# STM32.net
KiCad netlist of a schematic drawn in Altium Designer
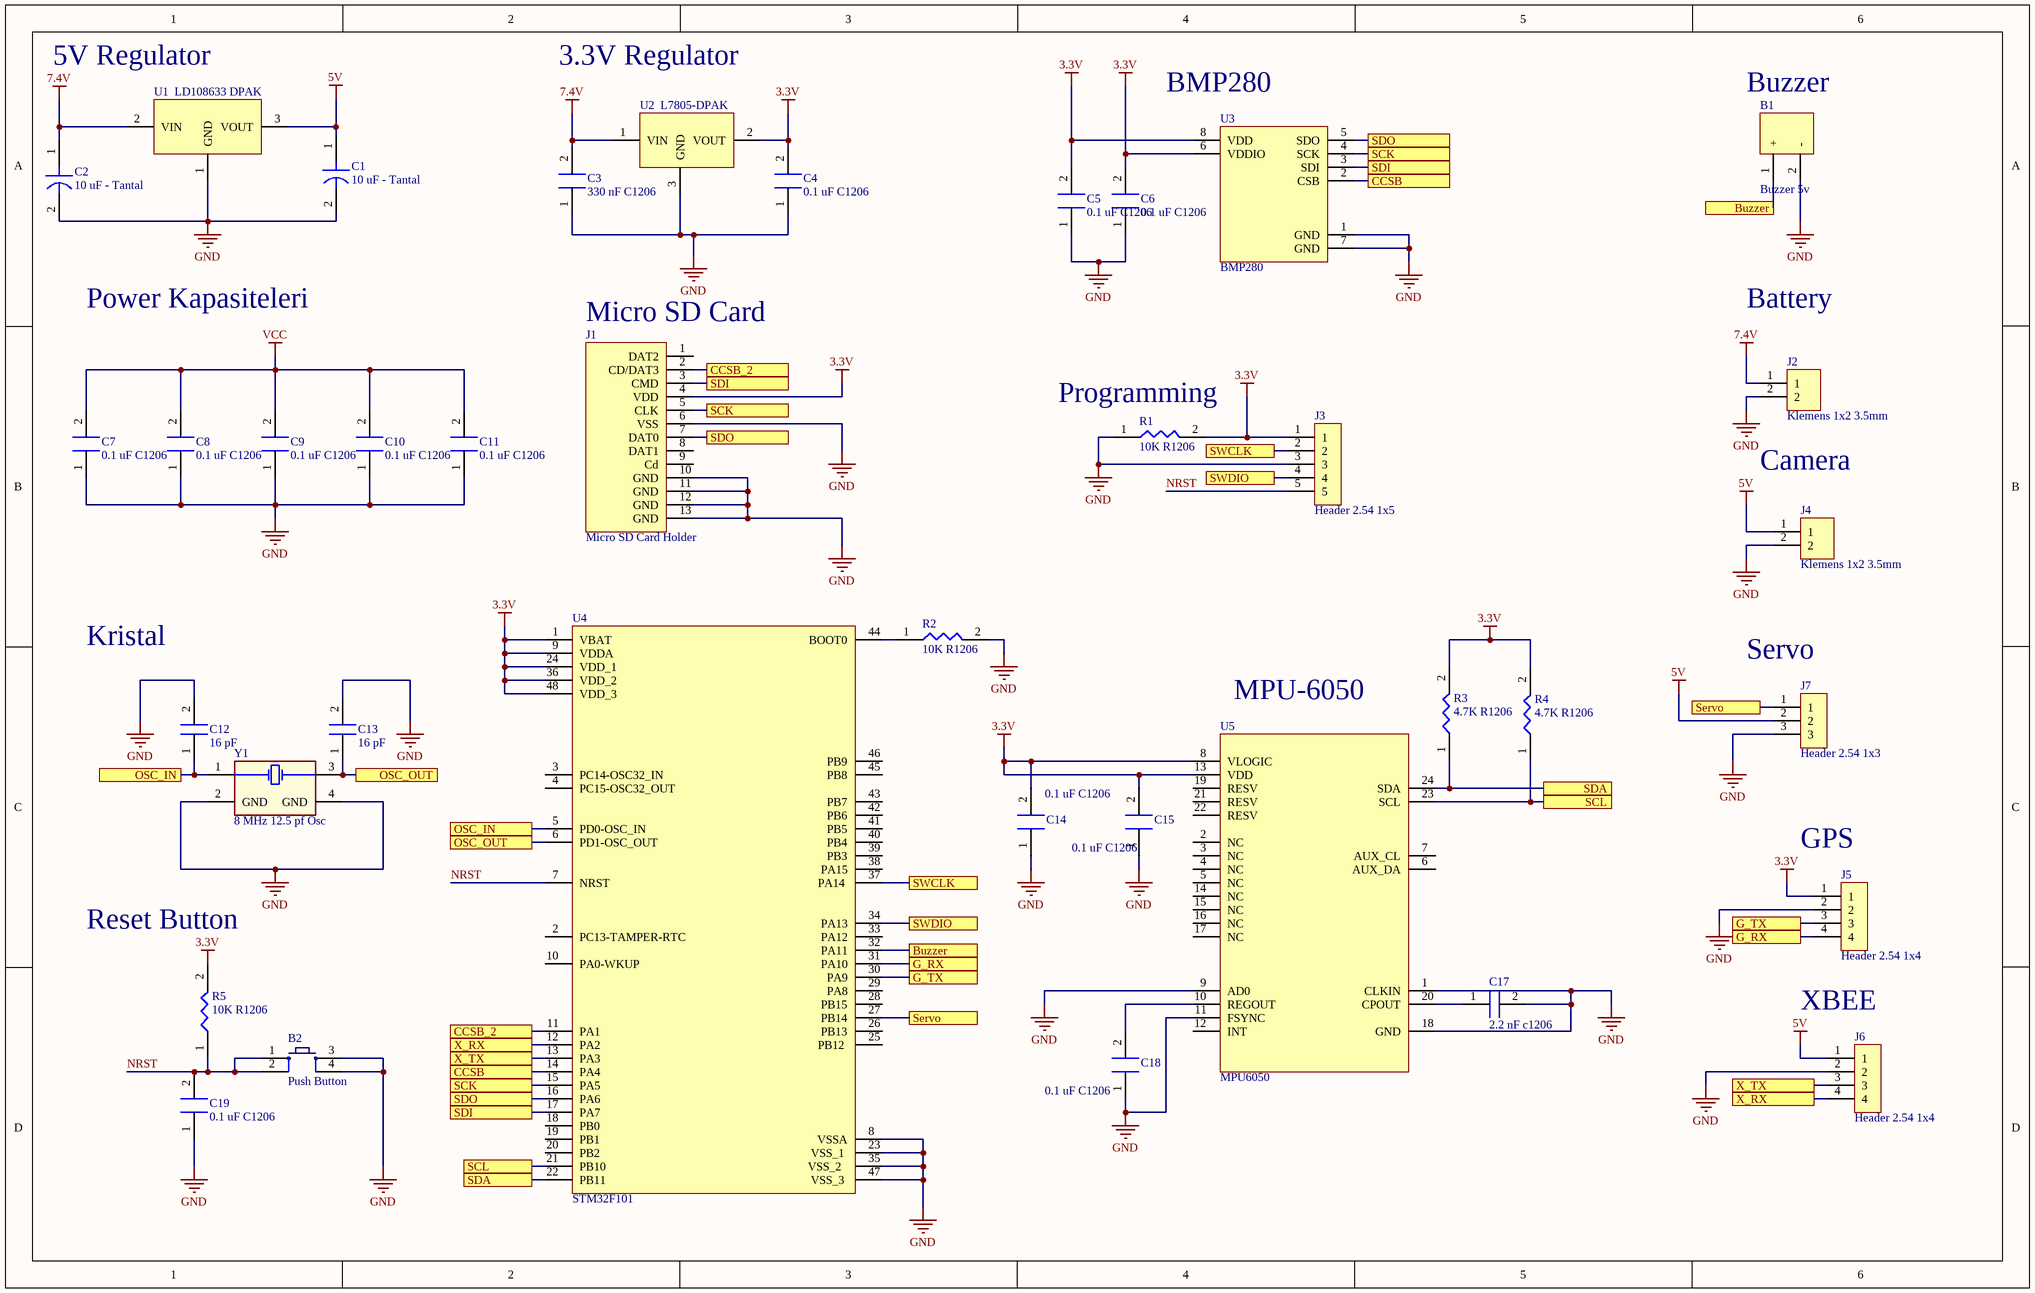
[diagram p0: STM32.SchDoc]

(export (version "E")
  (design (tool "Eeschema 10.0.6"))
  (components
    (comp (ref "B1") (value "Buzzer 5v") (footprint "Buzzer 5v") (libsource (lib "STM32") (part "Buzzer 5v")))
    (comp (ref "B2")
      (value "Push Button")
      (footprint "PUSB BUTTON-SMD")
      (description "Smd Push Button")
      (libsource (lib "STM32") (part "Push Button"))
    )
    (comp (ref "C1")
      (value "10 uF - Tantal")
      (footprint "C1206- TANTAL")
      (libsource (lib "STM32") (part "10 uF - Tantal"))
    )
    (comp (ref "C2")
      (value "10 uF - Tantal")
      (footprint "C1206- TANTAL")
      (libsource (lib "STM32") (part "10 uF - Tantal"))
    )
    (comp (ref "C3")
      (value "330 nF C1206")
      (footprint "C1206")
      (libsource (lib "STM32") (part "330 nF C1206"))
    )
    (comp (ref "C4")
      (value "0.1 uF C1206")
      (footprint "C1206")
      (libsource (lib "STM32") (part "0.1 uF C1206"))
    )
    (comp (ref "C5")
      (value "0.1 uF C1206")
      (footprint "C1206")
      (libsource (lib "STM32") (part "0.1 uF C1206"))
    )
    (comp (ref "C6")
      (value "0.1 uF C1206")
      (footprint "C1206")
      (libsource (lib "STM32") (part "0.1 uF C1206"))
    )
    (comp (ref "C7")
      (value "0.1 uF C1206")
      (footprint "C1206")
      (libsource (lib "STM32") (part "0.1 uF C1206"))
    )
    (comp (ref "C8")
      (value "0.1 uF C1206")
      (footprint "C1206")
      (libsource (lib "STM32") (part "0.1 uF C1206"))
    )
    (comp (ref "C9")
      (value "0.1 uF C1206")
      (footprint "C1206")
      (libsource (lib "STM32") (part "0.1 uF C1206"))
    )
    (comp (ref "C10")
      (value "0.1 uF C1206")
      (footprint "C1206")
      (libsource (lib "STM32") (part "0.1 uF C1206"))
    )
    (comp (ref "C11")
      (value "0.1 uF C1206")
      (footprint "C1206")
      (libsource (lib "STM32") (part "0.1 uF C1206"))
    )
    (comp (ref "C12") (value "16 pF") (footprint "C1206") (libsource (lib "STM32") (part "16 pF")))
    (comp (ref "C13") (value "16 pF") (footprint "C1206") (libsource (lib "STM32") (part "16 pF")))
    (comp (ref "C14")
      (value "0.1 uF C1206")
      (footprint "C1206")
      (libsource (lib "STM32") (part "0.1 uF C1206"))
    )
    (comp (ref "C15")
      (value "0.1 uF C1206")
      (footprint "C1206")
      (libsource (lib "STM32") (part "0.1 uF C1206"))
    )
    (comp (ref "C17")
      (value "2.2 nF c1206")
      (footprint "C1206")
      (libsource (lib "STM32") (part "2.2 nF c1206"))
    )
    (comp (ref "C18")
      (value "0.1 uF C1206")
      (footprint "C1206")
      (libsource (lib "STM32") (part "0.1 uF C1206"))
    )
    (comp (ref "C19")
      (value "0.1 uF C1206")
      (footprint "C1206")
      (libsource (lib "STM32") (part "0.1 uF C1206"))
    )
    (comp (ref "J1")
      (value "Micro SD Card Holder")
      (footprint "Micro SD Card Holder")
      (libsource (lib "STM32") (part "Micro SD Card Holder"))
    )
    (comp (ref "J2")
      (value "Klemens 1x2 3.5mm")
      (footprint "Klemens 1x2 - 3.5mm")
      (libsource (lib "STM32") (part "Klemens 1x2 3.5mm"))
    )
    (comp (ref "J3")
      (value "Header 2.54 1x5")
      (footprint "Header 2.54 1x5")
      (libsource (lib "STM32") (part "Header 2.54 1x5"))
    )
    (comp (ref "J4")
      (value "Klemens 1x2 3.5mm")
      (footprint "Klemens 1x2 - 3.5mm")
      (libsource (lib "STM32") (part "Klemens 1x2 3.5mm"))
    )
    (comp (ref "J5")
      (value "Header 2.54 1x4")
      (footprint "Header 2.54 1x4")
      (libsource (lib "STM32") (part "Header 2.54 1x4"))
    )
    (comp (ref "J6")
      (value "Header 2.54 1x4")
      (footprint "Header 2.54 1x4")
      (libsource (lib "STM32") (part "Header 2.54 1x4"))
    )
    (comp (ref "J7")
      (value "Header 2.54 1x3")
      (footprint "Header 2.54 1x3")
      (libsource (lib "STM32") (part "Header 2.54 1x3"))
    )
    (comp (ref "R1")
      (value "10K R1206")
      (footprint "R1206 Resıstor")
      (libsource (lib "STM32") (part "10K R1206"))
    )
    (comp (ref "R2")
      (value "10K R1206")
      (footprint "R1206 Resıstor")
      (libsource (lib "STM32") (part "10K R1206"))
    )
    (comp (ref "R3")
      (value "4.7K R1206")
      (footprint "R1206 Resıstor")
      (libsource (lib "STM32") (part "4.7K R1206"))
    )
    (comp (ref "R4")
      (value "4.7K R1206")
      (footprint "R1206 Resıstor")
      (libsource (lib "STM32") (part "4.7K R1206"))
    )
    (comp (ref "R5")
      (value "10K R1206")
      (footprint "R1206 Resıstor")
      (libsource (lib "STM32") (part "10K R1206"))
    )
    (comp (ref "U1")
      (value "LD108633 DPAK")
      (footprint "DPAK228P972X230-3N")
      (description "LD1086 3.3V REGULATOR")
      (libsource (lib "STM32") (part "LD108633 DPAK"))
    )
    (comp (ref "U2")
      (value "L7805-DPAK")
      (footprint "DPAK228P972X230-3N")
      (description "L7805 5V REGULATOR. SMD PAKET")
      (libsource (lib "STM32") (part "L7805-DPAK"))
    )
    (comp (ref "U3") (value "BMP280") (footprint "BMP280") (libsource (lib "STM32") (part "BMP280")))
    (comp (ref "U4")
      (value "STM32F101")
      (footprint "LQFP48-STM")
      (description "STM32F101 48 PİNLİ MİKROİŞLEMCİ")
      (libsource (lib "STM32") (part "STM32F101"))
    )
    (comp (ref "U5")
      (value "MPU6050")
      (footprint "QFN50P400X400X90_HS-25N")
      (description "MPU6050 GYRO")
      (libsource (lib "STM32") (part "MPU6050"))
    )
    (comp (ref "Y1")
      (value "8 MHz 12.5 pf Osc")
      (footprint "8 MHZ Osc.")
      (libsource (lib "STM32") (part "8 MHz 12.5 pf Osc"))
    )
  )
  (nets
    (net (code "1") (name "/Buzzer") (class "Default")
      (node (ref "B1") (pin "1") (pinfunction "+_1") (pintype "passive"))
      (node (ref "U4") (pin "32") (pinfunction "PA11_32") (pintype "passive"))
    )
    (net (code "2") (name "/CCSB") (class "Default")
      (node (ref "U3") (pin "2") (pinfunction "CSB_2") (pintype "passive"))
      (node (ref "U4") (pin "14") (pinfunction "PA4_14") (pintype "passive"))
    )
    (net (code "3") (name "/CCSB_2") (class "Default")
      (node (ref "J1") (pin "2") (pinfunction "CD/DAT3_2") (pintype "passive"))
      (node (ref "U4") (pin "11") (pinfunction "PA1_11") (pintype "passive"))
    )
    (net (code "4") (name "/G_RX") (class "Default")
      (node (ref "J5") (pin "4") (pinfunction "4_4") (pintype "passive"))
      (node (ref "U4") (pin "31") (pinfunction "PA10_31") (pintype "passive"))
    )
    (net (code "5") (name "/G_TX") (class "Default")
      (node (ref "J5") (pin "3") (pinfunction "3_3") (pintype "passive"))
      (node (ref "U4") (pin "30") (pinfunction "PA9_30") (pintype "passive"))
    )
    (net (code "6") (name "/NRST") (class "Default")
      (node (ref "B2") (pin "1") (pinfunction "1_1") (pintype "passive"))
      (node (ref "B2") (pin "2") (pinfunction "2_2") (pintype "passive"))
      (node (ref "C19") (pin "2") (pinfunction "2_2") (pintype "passive"))
      (node (ref "J3") (pin "5") (pinfunction "5_5") (pintype "passive"))
      (node (ref "R5") (pin "1") (pinfunction "1_1") (pintype "passive"))
      (node (ref "U4") (pin "7") (pinfunction "NRST_7") (pintype "passive"))
    )
    (net (code "7") (name "/OSC_IN") (class "Default")
      (node (ref "C12") (pin "1") (pinfunction "1_1") (pintype "passive"))
      (node (ref "U4") (pin "5") (pinfunction "PD0-OSC_IN_5") (pintype "passive"))
      (node (ref "Y1") (pin "1") (pintype "power_in"))
    )
    (net (code "8") (name "/OSC_OUT") (class "Default")
      (node (ref "C13") (pin "1") (pinfunction "1_1") (pintype "passive"))
      (node (ref "U4") (pin "6") (pinfunction "PD1-OSC_OUT_6") (pintype "passive"))
      (node (ref "Y1") (pin "3") (pintype "passive"))
    )
    (net (code "9") (name "/SCK") (class "Default")
      (node (ref "J1") (pin "5") (pinfunction "CLK_5") (pintype "passive"))
      (node (ref "U3") (pin "4") (pinfunction "SCK_4") (pintype "passive"))
      (node (ref "U4") (pin "15") (pinfunction "PA5_15") (pintype "passive"))
    )
    (net (code "10") (name "/SCL") (class "Default")
      (node (ref "R4") (pin "1") (pinfunction "1_1") (pintype "passive"))
      (node (ref "U4") (pin "21") (pinfunction "PB10_21") (pintype "passive"))
      (node (ref "U5") (pin "23") (pinfunction "SCL_23") (pintype "passive"))
    )
    (net (code "11") (name "/SDA") (class "Default")
      (node (ref "R3") (pin "1") (pinfunction "1_1") (pintype "passive"))
      (node (ref "U4") (pin "22") (pinfunction "PB11_22") (pintype "passive"))
      (node (ref "U5") (pin "24") (pinfunction "SDA_24") (pintype "passive"))
    )
    (net (code "12") (name "/SDI") (class "Default")
      (node (ref "J1") (pin "3") (pinfunction "CMD_3") (pintype "passive"))
      (node (ref "U3") (pin "3") (pinfunction "SDI_3") (pintype "passive"))
      (node (ref "U4") (pin "17") (pinfunction "PA7_17") (pintype "passive"))
    )
    (net (code "13") (name "/SDO") (class "Default")
      (node (ref "J1") (pin "7") (pinfunction "DAT0_7") (pintype "passive"))
      (node (ref "U3") (pin "5") (pinfunction "SDO_5") (pintype "passive"))
      (node (ref "U4") (pin "16") (pinfunction "PA6_16") (pintype "passive"))
    )
    (net (code "14") (name "/SWCLK") (class "Default")
      (node (ref "J3") (pin "2") (pinfunction "2_2") (pintype "passive"))
      (node (ref "U4") (pin "37") (pinfunction "PA14_37") (pintype "passive"))
    )
    (net (code "15") (name "/SWDIO") (class "Default")
      (node (ref "J3") (pin "4") (pinfunction "4_4") (pintype "passive"))
      (node (ref "U4") (pin "34") (pinfunction "PA13_34") (pintype "passive"))
    )
    (net (code "16") (name "/Servo") (class "Default")
      (node (ref "J7") (pin "1") (pinfunction "1_1") (pintype "passive"))
      (node (ref "U4") (pin "27") (pinfunction "PB14_27") (pintype "passive"))
    )
    (net (code "17") (name "/X_RX") (class "Default")
      (node (ref "J6") (pin "4") (pinfunction "4_4") (pintype "passive"))
      (node (ref "U4") (pin "12") (pinfunction "PA2_12") (pintype "passive"))
    )
    (net (code "18") (name "/X_TX") (class "Default")
      (node (ref "J6") (pin "3") (pinfunction "3_3") (pintype "passive"))
      (node (ref "U4") (pin "13") (pinfunction "PA3_13") (pintype "passive"))
    )
    (net (code "19") (name "3.3V") (class "Default")
      (node (ref "C14") (pin "2") (pinfunction "2_2") (pintype "passive"))
      (node (ref "C15") (pin "2") (pinfunction "2_2") (pintype "passive"))
      (node (ref "C4") (pin "2") (pinfunction "2_2") (pintype "passive"))
      (node (ref "C5") (pin "2") (pinfunction "2_2") (pintype "passive"))
      (node (ref "C6") (pin "2") (pinfunction "2_2") (pintype "passive"))
      (node (ref "J1") (pin "4") (pinfunction "VDD_4") (pintype "passive"))
      (node (ref "J3") (pin "1") (pinfunction "1_1") (pintype "passive"))
      (node (ref "J5") (pin "1") (pinfunction "1_1") (pintype "passive"))
      (node (ref "R1") (pin "2") (pinfunction "2_2") (pintype "passive"))
      (node (ref "R3") (pin "2") (pinfunction "2_2") (pintype "passive"))
      (node (ref "R4") (pin "2") (pinfunction "2_2") (pintype "passive"))
      (node (ref "R5") (pin "2") (pinfunction "2_2") (pintype "passive"))
      (node (ref "U2") (pin "2") (pinfunction "VOUT_2") (pintype "passive"))
      (node (ref "U3") (pin "6") (pinfunction "VDDIO_6") (pintype "passive"))
      (node (ref "U3") (pin "8") (pinfunction "VDD_8") (pintype "passive"))
      (node (ref "U4") (pin "1") (pinfunction "VBAT_1") (pintype "passive"))
      (node (ref "U4") (pin "24") (pinfunction "VDD_1_24") (pintype "passive"))
      (node (ref "U4") (pin "36") (pinfunction "VDD_2_36") (pintype "passive"))
      (node (ref "U4") (pin "48") (pinfunction "VDD_3_48") (pintype "passive"))
      (node (ref "U4") (pin "9") (pinfunction "VDDA_9") (pintype "passive"))
      (node (ref "U5") (pin "13") (pinfunction "VDD_13") (pintype "passive"))
      (node (ref "U5") (pin "8") (pinfunction "VLOGIC_8") (pintype "passive"))
    )
    (net (code "20") (name "5V") (class "Default")
      (node (ref "C1") (pin "1") (pinfunction "1_1") (pintype "passive"))
      (node (ref "J4") (pin "1") (pinfunction "1_1") (pintype "passive"))
      (node (ref "J6") (pin "1") (pinfunction "1_1") (pintype "passive"))
      (node (ref "J7") (pin "2") (pinfunction "2_2") (pintype "passive"))
      (node (ref "U1") (pin "3") (pinfunction "VOUT_3") (pintype "passive"))
    )
    (net (code "21") (name "7.4V") (class "Default")
      (node (ref "C2") (pin "1") (pinfunction "1_1") (pintype "passive"))
      (node (ref "C3") (pin "2") (pinfunction "2_2") (pintype "passive"))
      (node (ref "J2") (pin "1") (pinfunction "1_1") (pintype "passive"))
      (node (ref "U1") (pin "2") (pinfunction "VIN_2") (pintype "passive"))
      (node (ref "U2") (pin "1") (pinfunction "VIN_1") (pintype "passive"))
    )
    (net (code "22") (name "GND") (class "Default")
      (node (ref "B1") (pin "2") (pinfunction "-_2") (pintype "passive"))
      (node (ref "B2") (pin "3") (pinfunction "3_3") (pintype "passive"))
      (node (ref "B2") (pin "4") (pinfunction "4_4") (pintype "passive"))
      (node (ref "C1") (pin "2") (pinfunction "2_2") (pintype "passive"))
      (node (ref "C10") (pin "1") (pinfunction "1_1") (pintype "passive"))
      (node (ref "C11") (pin "1") (pinfunction "1_1") (pintype "passive"))
      (node (ref "C12") (pin "2") (pinfunction "2_2") (pintype "passive"))
      (node (ref "C13") (pin "2") (pinfunction "2_2") (pintype "passive"))
      (node (ref "C14") (pin "1") (pinfunction "1_1") (pintype "passive"))
      (node (ref "C15") (pin "1") (pinfunction "1_1") (pintype "passive"))
      (node (ref "C17") (pin "2") (pinfunction "2_2") (pintype "passive"))
      (node (ref "C18") (pin "1") (pinfunction "1_1") (pintype "passive"))
      (node (ref "C19") (pin "1") (pinfunction "1_1") (pintype "passive"))
      (node (ref "C2") (pin "2") (pinfunction "2_2") (pintype "passive"))
      (node (ref "C3") (pin "1") (pinfunction "1_1") (pintype "passive"))
      (node (ref "C4") (pin "1") (pinfunction "1_1") (pintype "passive"))
      (node (ref "C5") (pin "1") (pinfunction "1_1") (pintype "passive"))
      (node (ref "C6") (pin "1") (pinfunction "1_1") (pintype "passive"))
      (node (ref "C7") (pin "1") (pinfunction "1_1") (pintype "passive"))
      (node (ref "C8") (pin "1") (pinfunction "1_1") (pintype "passive"))
      (node (ref "C9") (pin "1") (pinfunction "1_1") (pintype "passive"))
      (node (ref "J1") (pin "10") (pinfunction "GND_10") (pintype "passive"))
      (node (ref "J1") (pin "11") (pinfunction "GND_11") (pintype "passive"))
      (node (ref "J1") (pin "12") (pinfunction "GND_12") (pintype "passive"))
      (node (ref "J1") (pin "13") (pinfunction "GND_13") (pintype "passive"))
      (node (ref "J1") (pin "6") (pinfunction "VSS_6") (pintype "passive"))
      (node (ref "J2") (pin "2") (pinfunction "2_2") (pintype "passive"))
      (node (ref "J3") (pin "3") (pinfunction "3_3") (pintype "passive"))
      (node (ref "J4") (pin "2") (pinfunction "2_2") (pintype "passive"))
      (node (ref "J5") (pin "2") (pinfunction "2_2") (pintype "passive"))
      (node (ref "J6") (pin "2") (pinfunction "2_2") (pintype "passive"))
      (node (ref "J7") (pin "3") (pinfunction "3_3") (pintype "passive"))
      (node (ref "R1") (pin "1") (pinfunction "1_1") (pintype "passive"))
      (node (ref "R2") (pin "2") (pinfunction "2_2") (pintype "passive"))
      (node (ref "U1") (pin "1") (pinfunction "GND_1") (pintype "passive"))
      (node (ref "U2") (pin "3") (pinfunction "GND_3") (pintype "passive"))
      (node (ref "U3") (pin "1") (pinfunction "GND_1") (pintype "passive"))
      (node (ref "U3") (pin "7") (pinfunction "GND_7") (pintype "passive"))
      (node (ref "U4") (pin "23") (pinfunction "VSS_1_23") (pintype "passive"))
      (node (ref "U4") (pin "35") (pinfunction "VSS_2_35") (pintype "passive"))
      (node (ref "U4") (pin "47") (pinfunction "VSS_3_47") (pintype "passive"))
      (node (ref "U4") (pin "8") (pinfunction "VSSA_8") (pintype "passive"))
      (node (ref "U5") (pin "1") (pinfunction "CLKIN_1") (pintype "passive"))
      (node (ref "U5") (pin "11") (pinfunction "FSYNC_11") (pintype "passive"))
      (node (ref "U5") (pin "18") (pinfunction "GND_18") (pintype "passive"))
      (node (ref "U5") (pin "9") (pinfunction "AD0_9") (pintype "passive"))
      (node (ref "Y1") (pin "2") (pinfunction "GND_2") (pintype "power_in"))
      (node (ref "Y1") (pin "4") (pinfunction "GND_4") (pintype "passive"))
    )
    (net (code "23") (name "Net-(U4-BOOT0)") (class "Default")
      (node (ref "R2") (pin "1") (pinfunction "1_1") (pintype "passive"))
      (node (ref "U4") (pin "44") (pinfunction "BOOT0_44") (pintype "passive"))
    )
    (net (code "24") (name "Net-(U5-CPOUT)") (class "Default")
      (node (ref "C17") (pin "1") (pinfunction "1_1") (pintype "passive"))
      (node (ref "U5") (pin "20") (pinfunction "CPOUT_20") (pintype "passive"))
    )
    (net (code "25") (name "Net-(U5-REGOUT)") (class "Default")
      (node (ref "C18") (pin "2") (pinfunction "2_2") (pintype "passive"))
      (node (ref "U5") (pin "10") (pinfunction "REGOUT_10") (pintype "passive"))
    )
    (net (code "26") (name "VCC") (class "Default")
      (node (ref "C10") (pin "2") (pinfunction "2_2") (pintype "passive"))
      (node (ref "C11") (pin "2") (pinfunction "2_2") (pintype "passive"))
      (node (ref "C7") (pin "2") (pinfunction "2_2") (pintype "passive"))
      (node (ref "C8") (pin "2") (pinfunction "2_2") (pintype "passive"))
      (node (ref "C9") (pin "2") (pinfunction "2_2") (pintype "passive"))
    )
    (net (code "27") (name "unconnected-(J1-Cd-Pad9)") (class "Default")
      (node (ref "J1") (pin "9") (pinfunction "Cd_9") (pintype "passive"))
    )
    (net (code "28") (name "unconnected-(J1-DAT1-Pad8)") (class "Default")
      (node (ref "J1") (pin "8") (pinfunction "DAT1_8") (pintype "passive"))
    )
    (net (code "29") (name "unconnected-(J1-DAT2-Pad1)") (class "Default")
      (node (ref "J1") (pin "1") (pinfunction "DAT2_1") (pintype "passive"))
    )
    (net (code "30") (name "unconnected-(U4-PA0-WKUP-Pad10)") (class "Default")
      (node (ref "U4") (pin "10") (pinfunction "PA0-WKUP_10") (pintype "passive"))
    )
    (net (code "31") (name "unconnected-(U4-PA8-Pad29)") (class "Default")
      (node (ref "U4") (pin "29") (pinfunction "PA8_29") (pintype "passive"))
    )
    (net (code "32") (name "unconnected-(U4-PA12-Pad33)") (class "Default")
      (node (ref "U4") (pin "33") (pinfunction "PA12_33") (pintype "passive"))
    )
    (net (code "33") (name "unconnected-(U4-PA15-Pad38)") (class "Default")
      (node (ref "U4") (pin "38") (pinfunction "PA15_38") (pintype "passive"))
    )
    (net (code "34") (name "unconnected-(U4-PB0-Pad18)") (class "Default")
      (node (ref "U4") (pin "18") (pinfunction "PB0_18") (pintype "passive"))
    )
    (net (code "35") (name "unconnected-(U4-PB1-Pad19)") (class "Default")
      (node (ref "U4") (pin "19") (pinfunction "PB1_19") (pintype "passive"))
    )
    (net (code "36") (name "unconnected-(U4-PB2-Pad20)") (class "Default")
      (node (ref "U4") (pin "20") (pinfunction "PB2_20") (pintype "passive"))
    )
    (net (code "37") (name "unconnected-(U4-PB3-Pad39)") (class "Default")
      (node (ref "U4") (pin "39") (pinfunction "PB3_39") (pintype "passive"))
    )
    (net (code "38") (name "unconnected-(U4-PB4-Pad40)") (class "Default")
      (node (ref "U4") (pin "40") (pinfunction "PB4_40") (pintype "passive"))
    )
    (net (code "39") (name "unconnected-(U4-PB5-Pad41)") (class "Default")
      (node (ref "U4") (pin "41") (pinfunction "PB5_41") (pintype "passive"))
    )
    (net (code "40") (name "unconnected-(U4-PB6-Pad42)") (class "Default")
      (node (ref "U4") (pin "42") (pinfunction "PB6_42") (pintype "passive"))
    )
    (net (code "41") (name "unconnected-(U4-PB7-Pad43)") (class "Default")
      (node (ref "U4") (pin "43") (pinfunction "PB7_43") (pintype "passive"))
    )
    (net (code "42") (name "unconnected-(U4-PB8-Pad45)") (class "Default")
      (node (ref "U4") (pin "45") (pinfunction "PB8_45") (pintype "passive"))
    )
    (net (code "43") (name "unconnected-(U4-PB9-Pad46)") (class "Default")
      (node (ref "U4") (pin "46") (pinfunction "PB9_46") (pintype "passive"))
    )
    (net (code "44") (name "unconnected-(U4-PB12-Pad25)") (class "Default")
      (node (ref "U4") (pin "25") (pinfunction "PB12_25") (pintype "passive"))
    )
    (net (code "45") (name "unconnected-(U4-PB13-Pad26)") (class "Default")
      (node (ref "U4") (pin "26") (pinfunction "PB13_26") (pintype "passive"))
    )
    (net (code "46") (name "unconnected-(U4-PB15-Pad28)") (class "Default")
      (node (ref "U4") (pin "28") (pinfunction "PB15_28") (pintype "passive"))
    )
    (net (code "47") (name "unconnected-(U4-PC13-TAMPER-RTC-Pad2)") (class "Default")
      (node (ref "U4") (pin "2") (pinfunction "PC13-TAMPER-RTC_2") (pintype "passive"))
    )
    (net (code "48") (name "unconnected-(U4-PC14-OSC32_IN-Pad3)") (class "Default")
      (node (ref "U4") (pin "3") (pinfunction "PC14-OSC32_IN_3") (pintype "passive"))
    )
    (net (code "49") (name "unconnected-(U4-PC15-OSC32_OUT-Pad4)") (class "Default")
      (node (ref "U4") (pin "4") (pinfunction "PC15-OSC32_OUT_4") (pintype "passive"))
    )
    (net (code "50") (name "unconnected-(U5-AUX_CL-Pad7)") (class "Default")
      (node (ref "U5") (pin "7") (pinfunction "AUX_CL_7") (pintype "passive"))
    )
    (net (code "51") (name "unconnected-(U5-AUX_DA-Pad6)") (class "Default")
      (node (ref "U5") (pin "6") (pinfunction "AUX_DA_6") (pintype "passive"))
    )
    (net (code "52") (name "unconnected-(U5-INT-Pad12)") (class "Default")
      (node (ref "U5") (pin "12") (pinfunction "INT_12") (pintype "passive"))
    )
    (net (code "53") (name "unconnected-(U5-NC-Pad2)") (class "Default")
      (node (ref "U5") (pin "2") (pinfunction "NC_2") (pintype "passive"))
    )
    (net (code "54") (name "unconnected-(U5-NC-Pad3)") (class "Default")
      (node (ref "U5") (pin "3") (pinfunction "NC_3") (pintype "passive"))
    )
    (net (code "55") (name "unconnected-(U5-NC-Pad4)") (class "Default")
      (node (ref "U5") (pin "4") (pinfunction "NC_4") (pintype "passive"))
    )
    (net (code "56") (name "unconnected-(U5-NC-Pad5)") (class "Default")
      (node (ref "U5") (pin "5") (pinfunction "NC_5") (pintype "passive"))
    )
    (net (code "57") (name "unconnected-(U5-NC-Pad14)") (class "Default")
      (node (ref "U5") (pin "14") (pinfunction "NC_14") (pintype "passive"))
    )
    (net (code "58") (name "unconnected-(U5-NC-Pad15)") (class "Default")
      (node (ref "U5") (pin "15") (pinfunction "NC_15") (pintype "passive"))
    )
    (net (code "59") (name "unconnected-(U5-NC-Pad16)") (class "Default")
      (node (ref "U5") (pin "16") (pinfunction "NC_16") (pintype "passive"))
    )
    (net (code "60") (name "unconnected-(U5-NC-Pad17)") (class "Default")
      (node (ref "U5") (pin "17") (pinfunction "NC_17") (pintype "passive"))
    )
    (net (code "61") (name "unconnected-(U5-RESV-Pad19)") (class "Default")
      (node (ref "U5") (pin "19") (pinfunction "RESV_19") (pintype "passive"))
    )
    (net (code "62") (name "unconnected-(U5-RESV-Pad21)") (class "Default")
      (node (ref "U5") (pin "21") (pinfunction "RESV_21") (pintype "passive"))
    )
    (net (code "63") (name "unconnected-(U5-RESV-Pad22)") (class "Default")
      (node (ref "U5") (pin "22") (pinfunction "RESV_22") (pintype "passive"))
    )
  )
)
